# MFU_1_00.net
KiCad netlist of a schematic drawn in Altium Designer
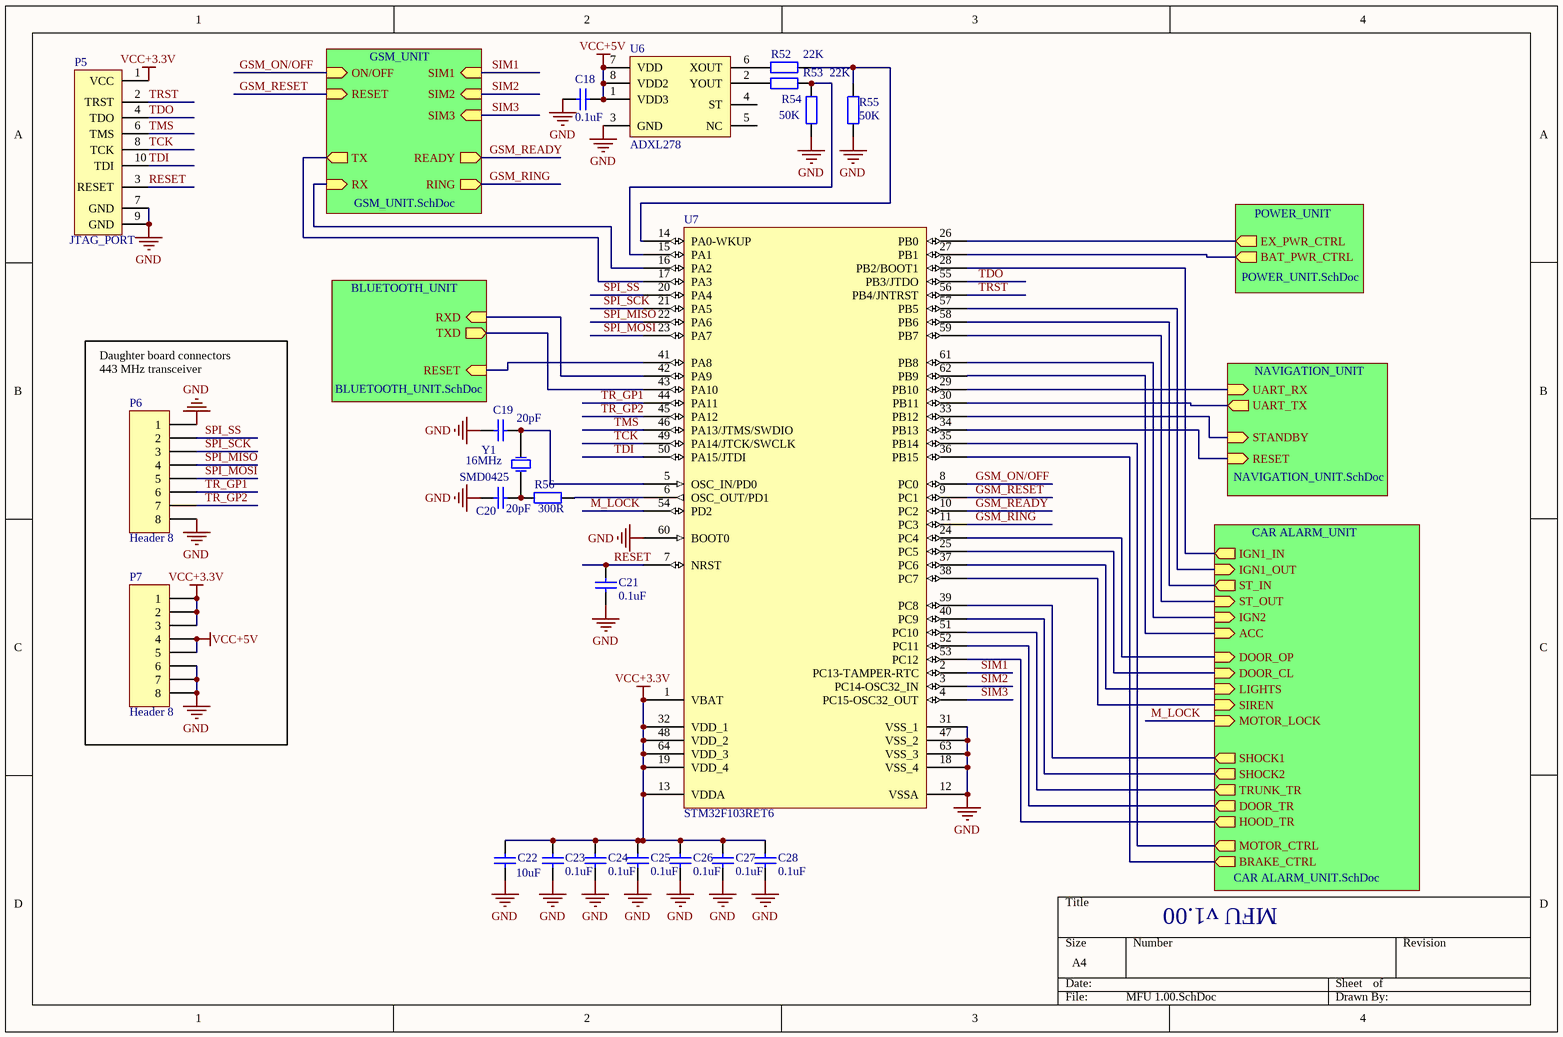
[diagram p0: MFU 1.00.SchDoc]

(export (version "E")
  (design (tool "Eeschema 10.0.6"))
  (components
    (comp (ref "C18")
      (value "0.1uF")
      (footprint "C0603")
      (description "Capasitor_SMD_0808/")
      (fields (field (name "Comment") "0805"))
      (libsource (lib "NEW") (part "Capasitor_SMD_0805"))
    )
    (comp (ref "C19")
      (value "20pF")
      (footprint "C0603")
      (description "Capasitor_SMD_0808/")
      (fields (field (name "Comment") "0805"))
      (libsource (lib "NEW") (part "Capasitor_SMD_0805"))
    )
    (comp (ref "C20")
      (value "20pF")
      (footprint "C0603")
      (description "Capasitor_SMD_0808/")
      (fields (field (name "Comment") "0805"))
      (libsource (lib "NEW") (part "Capasitor_SMD_0805"))
    )
    (comp (ref "C21")
      (value "0.1uF")
      (footprint "C0603")
      (description "Capasitor_SMD_0808/")
      (fields (field (name "Comment") "0805"))
      (libsource (lib "NEW") (part "Capasitor_SMD_0805"))
    )
    (comp (ref "C22")
      (value "10uF")
      (footprint "C1210")
      (description "Capacitor (Semiconductor SIM Model)")
      (fields (field (name "Comment") "Cap Semi") (field (name "PUBLISHER") "Altium Limited"))
      (libsource (lib "Miscellaneous Devices") (part "Cap Semi"))
    )
    (comp (ref "C23")
      (value "0.1uF")
      (footprint "C0603")
      (description "Capasitor_SMD_0808/")
      (fields (field (name "Comment") "0805"))
      (libsource (lib "NEW") (part "Capasitor_SMD_0805"))
    )
    (comp (ref "C24")
      (value "0.1uF")
      (footprint "C0603")
      (description "Capasitor_SMD_0808/")
      (fields (field (name "Comment") "0805"))
      (libsource (lib "NEW") (part "Capasitor_SMD_0805"))
    )
    (comp (ref "C25")
      (value "0.1uF")
      (footprint "C0603")
      (description "Capasitor_SMD_0808/")
      (fields (field (name "Comment") "0805"))
      (libsource (lib "NEW") (part "Capasitor_SMD_0805"))
    )
    (comp (ref "C26")
      (value "0.1uF")
      (footprint "C0603")
      (description "Capasitor_SMD_0808/")
      (fields (field (name "Comment") "0805"))
      (libsource (lib "NEW") (part "Capasitor_SMD_0805"))
    )
    (comp (ref "C27")
      (value "0.1uF")
      (footprint "C0603")
      (description "Capasitor_SMD_0808/")
      (fields (field (name "Comment") "0805"))
      (libsource (lib "NEW") (part "Capasitor_SMD_0805"))
    )
    (comp (ref "C28")
      (value "0.1uF")
      (footprint "C0603")
      (description "Capasitor_SMD_0808/")
      (fields (field (name "Comment") "0805"))
      (libsource (lib "NEW") (part "Capasitor_SMD_0805"))
    )
    (comp (ref "P5")
      (value "JTAG_PORT")
      (footprint "JTAG_connector")
      (libsource (lib "NEW") (part "JTAG_port"))
    )
    (comp (ref "P6")
      (value "Header 8")
      (footprint "HDR1X8")
      (description "Header, 8-Pin")
      (fields (field (name "PUBLISHER") "Altium Limited"))
      (libsource (lib "Miscellaneous Connectors") (part "Header 8"))
    )
    (comp (ref "P7")
      (value "Header 8")
      (footprint "HDR1X8")
      (description "Header, 8-Pin")
      (fields (field (name "PUBLISHER") "Altium Limited"))
      (libsource (lib "Miscellaneous Connectors") (part "Header 8"))
    )
    (comp (ref "R52")
      (value "22K")
      (footprint "C0603")
      (description "Resistor")
      (fields (field (name "Comment") "RES"))
      (libsource (lib "NEW") (part "RES"))
    )
    (comp (ref "R53")
      (value "22K")
      (footprint "C0603")
      (description "Resistor")
      (fields (field (name "Comment") "RES"))
      (libsource (lib "NEW") (part "RES"))
    )
    (comp (ref "R54")
      (value "50K")
      (footprint "C0603")
      (description "Resistor")
      (fields (field (name "Comment") "RES"))
      (libsource (lib "") (part "RES_2"))
    )
    (comp (ref "R55")
      (value "50K")
      (footprint "C0603")
      (description "Resistor")
      (fields (field (name "Comment") "RES"))
      (libsource (lib "") (part "RES_2"))
    )
    (comp (ref "R56")
      (value "300R")
      (footprint "C0603")
      (description "Resistor")
      (fields (field (name "Comment") "RES"))
      (libsource (lib "") (part "RES_1"))
    )
    (comp (ref "U6") (value "ADXL278") (footprint "ADXL278") (libsource (lib "NEW") (part "ADXL278")))
    (comp (ref "U7")
      (value "STM32F103RET6")
      (footprint "LQFP64_M")
      (description "STM32 ARM-based 32-bit MCU with 512 Kbytes Flash, 64-pin LQFP, Industrial Temperature")
      (fields (field (name "PUBLISHER") "Altium Limited"))
      (libsource (lib "ST Microcontroller 32-Bit STM32") (part "STM32F103RBT6"))
    )
    (comp (ref "Y1")
      (value "SMD0425")
      (footprint "QUARTZ_SMD0425")
      (fields (field (name "ALTIUM_VALUE") "16MHz"))
      (libsource (lib "NEW") (part "Quartz_SMD"))
    )
  )
  (nets
    (net (code "1") (name "/ACC") (class "Default")
      (node (ref "U7") (pin "62") (pinfunction "PB9_62") (pintype "bidirectional"))
    )
    (net (code "2") (name "/BAT_PWR_CTRL") (class "Default")
      (node (ref "U7") (pin "27") (pinfunction "PB1_27") (pintype "bidirectional"))
    )
    (net (code "3") (name "/BRAKE_CTRL") (class "Default")
      (node (ref "U7") (pin "36") (pinfunction "PB15_36") (pintype "bidirectional"))
    )
    (net (code "4") (name "/DOOR_CL") (class "Default")
      (node (ref "U7") (pin "25") (pinfunction "PC5_25") (pintype "bidirectional"))
    )
    (net (code "5") (name "/DOOR_OP") (class "Default")
      (node (ref "U7") (pin "24") (pinfunction "PC4_24") (pintype "bidirectional"))
    )
    (net (code "6") (name "/DOOR_TR") (class "Default")
      (node (ref "U7") (pin "52") (pinfunction "PC11_52") (pintype "bidirectional"))
    )
    (net (code "7") (name "/EX_PWR_CTRL") (class "Default")
      (node (ref "U7") (pin "26") (pinfunction "PB0_26") (pintype "bidirectional"))
    )
    (net (code "8") (name "/GSM_ON{slash}OFF") (class "Default")
      (node (ref "U7") (pin "8") (pinfunction "PC0_8") (pintype "bidirectional"))
    )
    (net (code "9") (name "/GSM_READY") (class "Default")
      (node (ref "U7") (pin "10") (pinfunction "PC2_10") (pintype "bidirectional"))
    )
    (net (code "10") (name "/GSM_RESET") (class "Default")
      (node (ref "U7") (pin "9") (pinfunction "PC1_9") (pintype "bidirectional"))
    )
    (net (code "11") (name "/GSM_RING") (class "Default")
      (node (ref "U7") (pin "11") (pinfunction "PC3_11") (pintype "bidirectional"))
    )
    (net (code "12") (name "/HOOD_TR") (class "Default")
      (node (ref "U7") (pin "53") (pinfunction "PC12_53") (pintype "bidirectional"))
    )
    (net (code "13") (name "/IGN1_IN") (class "Default")
      (node (ref "U7") (pin "28") (pinfunction "PB2/BOOT1_28") (pintype "bidirectional"))
    )
    (net (code "14") (name "/IGN1_OUT") (class "Default")
      (node (ref "U7") (pin "57") (pinfunction "PB5_57") (pintype "bidirectional"))
    )
    (net (code "15") (name "/IGN2") (class "Default")
      (node (ref "U7") (pin "61") (pinfunction "PB8_61") (pintype "bidirectional"))
    )
    (net (code "16") (name "/LIGHTS") (class "Default")
      (node (ref "U7") (pin "37") (pinfunction "PC6_37") (pintype "bidirectional"))
    )
    (net (code "17") (name "/MOTOR_CTRL") (class "Default")
      (node (ref "U7") (pin "35") (pinfunction "PB14_35") (pintype "bidirectional"))
    )
    (net (code "18") (name "/M_LOCK") (class "Default")
      (node (ref "U7") (pin "54") (pinfunction "PD2_54") (pintype "bidirectional"))
    )
    (net (code "19") (name "/RESET") (class "Default")
      (node (ref "C21") (pin "2") (pinfunction "2_2") (pintype "passive"))
      (node (ref "P5") (pin "3") (pinfunction "RESET_3") (pintype "passive"))
      (node (ref "U7") (pin "7") (pinfunction "NRST_7") (pintype "bidirectional"))
    )
    (net (code "20") (name "/RESET_1") (class "Default")
      (node (ref "U7") (pin "34") (pinfunction "PB13_34") (pintype "bidirectional"))
    )
    (net (code "21") (name "/RESET_2") (class "Default")
      (node (ref "U7") (pin "41") (pinfunction "PA8_41") (pintype "bidirectional"))
    )
    (net (code "22") (name "/RX") (class "Default")
      (node (ref "U7") (pin "16") (pinfunction "PA2_16") (pintype "bidirectional"))
    )
    (net (code "23") (name "/RXD") (class "Default")
      (node (ref "U7") (pin "42") (pinfunction "PA9_42") (pintype "bidirectional"))
    )
    (net (code "24") (name "/SHOCK1") (class "Default")
      (node (ref "U7") (pin "39") (pinfunction "PC8_39") (pintype "bidirectional"))
    )
    (net (code "25") (name "/SHOCK2") (class "Default")
      (node (ref "U7") (pin "40") (pinfunction "PC9_40") (pintype "bidirectional"))
    )
    (net (code "26") (name "/SIM1") (class "Default")
      (node (ref "U7") (pin "2") (pinfunction "PC13-TAMPER-RTC_2") (pintype "bidirectional"))
    )
    (net (code "27") (name "/SIM2") (class "Default")
      (node (ref "U7") (pin "3") (pinfunction "PC14-OSC32_IN_3") (pintype "bidirectional"))
    )
    (net (code "28") (name "/SIM3") (class "Default")
      (node (ref "U7") (pin "4") (pinfunction "PC15-OSC32_OUT_4") (pintype "bidirectional"))
    )
    (net (code "29") (name "/SIREN") (class "Default")
      (node (ref "U7") (pin "38") (pinfunction "PC7_38") (pintype "bidirectional"))
    )
    (net (code "30") (name "/SPI_MISO") (class "Default")
      (node (ref "P6") (pin "4") (pinfunction "4_4") (pintype "passive"))
      (node (ref "U7") (pin "22") (pinfunction "PA6_22") (pintype "bidirectional"))
    )
    (net (code "31") (name "/SPI_MOSI") (class "Default")
      (node (ref "P6") (pin "5") (pinfunction "5_5") (pintype "passive"))
      (node (ref "U7") (pin "23") (pinfunction "PA7_23") (pintype "bidirectional"))
    )
    (net (code "32") (name "/SPI_SCK") (class "Default")
      (node (ref "P6") (pin "3") (pinfunction "3_3") (pintype "passive"))
      (node (ref "U7") (pin "21") (pinfunction "PA5_21") (pintype "bidirectional"))
    )
    (net (code "33") (name "/SPI_SS") (class "Default")
      (node (ref "P6") (pin "2") (pinfunction "2_2") (pintype "passive"))
      (node (ref "U7") (pin "20") (pinfunction "PA4_20") (pintype "bidirectional"))
    )
    (net (code "34") (name "/STANDBY") (class "Default")
      (node (ref "U7") (pin "33") (pinfunction "PB12_33") (pintype "bidirectional"))
    )
    (net (code "35") (name "/ST_IN") (class "Default")
      (node (ref "U7") (pin "58") (pinfunction "PB6_58") (pintype "bidirectional"))
    )
    (net (code "36") (name "/ST_OUT") (class "Default")
      (node (ref "U7") (pin "59") (pinfunction "PB7_59") (pintype "bidirectional"))
    )
    (net (code "37") (name "/TCK") (class "Default")
      (node (ref "P5") (pin "8") (pinfunction "TCK_8") (pintype "passive"))
      (node (ref "U7") (pin "49") (pinfunction "PA14/JTCK/SWCLK_49") (pintype "bidirectional"))
    )
    (net (code "38") (name "/TDI") (class "Default")
      (node (ref "P5") (pin "10") (pinfunction "TDI_10") (pintype "passive"))
      (node (ref "U7") (pin "50") (pinfunction "PA15/JTDI_50") (pintype "bidirectional"))
    )
    (net (code "39") (name "/TDO") (class "Default")
      (node (ref "P5") (pin "4") (pinfunction "TDO_4") (pintype "passive"))
      (node (ref "U7") (pin "55") (pinfunction "PB3/JTDO_55") (pintype "bidirectional"))
    )
    (net (code "40") (name "/TMS") (class "Default")
      (node (ref "P5") (pin "6") (pinfunction "TMS_6") (pintype "passive"))
      (node (ref "U7") (pin "46") (pinfunction "PA13/JTMS/SWDIO_46") (pintype "bidirectional"))
    )
    (net (code "41") (name "/TRST") (class "Default")
      (node (ref "P5") (pin "2") (pinfunction "TRST_2") (pintype "passive"))
      (node (ref "U7") (pin "56") (pinfunction "PB4/JNTRST_56") (pintype "bidirectional"))
    )
    (net (code "42") (name "/TRUNK_TR") (class "Default")
      (node (ref "U7") (pin "51") (pinfunction "PC10_51") (pintype "bidirectional"))
    )
    (net (code "43") (name "/TR_GP1") (class "Default")
      (node (ref "P6") (pin "6") (pinfunction "6_6") (pintype "passive"))
      (node (ref "U7") (pin "44") (pinfunction "PA11_44") (pintype "bidirectional"))
    )
    (net (code "44") (name "/TR_GP2") (class "Default")
      (node (ref "P6") (pin "7") (pinfunction "7_7") (pintype "passive"))
      (node (ref "U7") (pin "45") (pinfunction "PA12_45") (pintype "bidirectional"))
    )
    (net (code "45") (name "/TX") (class "Default")
      (node (ref "U7") (pin "17") (pinfunction "PA3_17") (pintype "bidirectional"))
    )
    (net (code "46") (name "/TXD") (class "Default")
      (node (ref "U7") (pin "43") (pinfunction "PA10_43") (pintype "bidirectional"))
    )
    (net (code "47") (name "/UART_RX") (class "Default")
      (node (ref "U7") (pin "29") (pinfunction "PB10_29") (pintype "bidirectional"))
    )
    (net (code "48") (name "/UART_TX") (class "Default")
      (node (ref "U7") (pin "30") (pinfunction "PB11_30") (pintype "bidirectional"))
    )
    (net (code "49") (name "GND") (class "Default")
      (node (ref "C18") (pin "1") (pinfunction "1_1") (pintype "passive"))
      (node (ref "C19") (pin "2") (pinfunction "2_2") (pintype "passive"))
      (node (ref "C20") (pin "2") (pinfunction "2_2") (pintype "passive"))
      (node (ref "C21") (pin "1") (pinfunction "1_1") (pintype "passive"))
      (node (ref "C22") (pin "1") (pinfunction "1_1") (pintype "passive"))
      (node (ref "C23") (pin "1") (pinfunction "1_1") (pintype "passive"))
      (node (ref "C24") (pin "1") (pinfunction "1_1") (pintype "passive"))
      (node (ref "C25") (pin "1") (pinfunction "1_1") (pintype "passive"))
      (node (ref "C26") (pin "1") (pinfunction "1_1") (pintype "passive"))
      (node (ref "C27") (pin "1") (pinfunction "1_1") (pintype "passive"))
      (node (ref "C28") (pin "1") (pinfunction "1_1") (pintype "passive"))
      (node (ref "P5") (pin "7") (pinfunction "GND_7") (pintype "passive"))
      (node (ref "P5") (pin "9") (pinfunction "GND_9") (pintype "passive"))
      (node (ref "P6") (pin "1") (pinfunction "1_1") (pintype "passive"))
      (node (ref "P6") (pin "8") (pinfunction "8_8") (pintype "passive"))
      (node (ref "P7") (pin "6") (pinfunction "6_6") (pintype "passive"))
      (node (ref "P7") (pin "7") (pinfunction "7_7") (pintype "passive"))
      (node (ref "P7") (pin "8") (pinfunction "8_8") (pintype "passive"))
      (node (ref "R54") (pin "2") (pinfunction "2_2") (pintype "passive"))
      (node (ref "R55") (pin "2") (pinfunction "2_2") (pintype "passive"))
      (node (ref "U6") (pin "3") (pinfunction "GND_3") (pintype "passive"))
      (node (ref "U7") (pin "12") (pinfunction "VSSA_12") (pintype "power_in"))
      (node (ref "U7") (pin "18") (pinfunction "VSS_4_18") (pintype "power_in"))
      (node (ref "U7") (pin "31") (pinfunction "VSS_1_31") (pintype "power_in"))
      (node (ref "U7") (pin "47") (pinfunction "VSS_2_47") (pintype "power_in"))
      (node (ref "U7") (pin "60") (pinfunction "BOOT0_60") (pintype "input"))
      (node (ref "U7") (pin "63") (pinfunction "VSS_3_63") (pintype "power_in"))
    )
    (net (code "50") (name "Net-(U6-XOUT)") (class "Default")
      (node (ref "R52") (pin "2") (pinfunction "2_2") (pintype "passive"))
      (node (ref "U6") (pin "6") (pinfunction "XOUT_6") (pintype "passive"))
    )
    (net (code "51") (name "Net-(U6-YOUT)") (class "Default")
      (node (ref "R53") (pin "2") (pinfunction "2_2") (pintype "passive"))
      (node (ref "U6") (pin "2") (pinfunction "YOUT_2") (pintype "passive"))
    )
    (net (code "52") (name "Net-(U7-OSC_IN{slash}PD0)") (class "Default")
      (node (ref "C19") (pin "1") (pinfunction "1_1") (pintype "passive"))
      (node (ref "U7") (pin "5") (pinfunction "OSC_IN/PD0_5") (pintype "input"))
      (node (ref "Y1") (pin "3") (pinfunction "OSC2_3") (pintype "passive"))
    )
    (net (code "53") (name "Net-(U7-OSC_OUT{slash}PD1)") (class "Default")
      (node (ref "R56") (pin "2") (pinfunction "2_2") (pintype "passive"))
      (node (ref "U7") (pin "6") (pinfunction "OSC_OUT/PD1_6") (pintype "output"))
    )
    (net (code "54") (name "Net-(U7-PA0-WKUP)") (class "Default")
      (node (ref "R52") (pin "1") (pinfunction "1_1") (pintype "passive"))
      (node (ref "R55") (pin "1") (pinfunction "1_1") (pintype "passive"))
      (node (ref "U7") (pin "14") (pinfunction "PA0-WKUP_14") (pintype "bidirectional"))
    )
    (net (code "55") (name "Net-(U7-PA1)") (class "Default")
      (node (ref "R53") (pin "1") (pinfunction "1_1") (pintype "passive"))
      (node (ref "R54") (pin "1") (pinfunction "1_1") (pintype "passive"))
      (node (ref "U7") (pin "15") (pinfunction "PA1_15") (pintype "bidirectional"))
    )
    (net (code "56") (name "Net-(Y1-OSC1)") (class "Default")
      (node (ref "C20") (pin "1") (pinfunction "1_1") (pintype "passive"))
      (node (ref "R56") (pin "1") (pinfunction "1_1") (pintype "passive"))
      (node (ref "Y1") (pin "1") (pinfunction "OSC1_1") (pintype "passive"))
    )
    (net (code "57") (name "VCC+3.3V") (class "Default")
      (node (ref "C22") (pin "2") (pinfunction "2_2") (pintype "passive"))
      (node (ref "C23") (pin "2") (pinfunction "2_2") (pintype "passive"))
      (node (ref "C24") (pin "2") (pinfunction "2_2") (pintype "passive"))
      (node (ref "C25") (pin "2") (pinfunction "2_2") (pintype "passive"))
      (node (ref "C26") (pin "2") (pinfunction "2_2") (pintype "passive"))
      (node (ref "C27") (pin "2") (pinfunction "2_2") (pintype "passive"))
      (node (ref "C28") (pin "2") (pinfunction "2_2") (pintype "passive"))
      (node (ref "P5") (pin "1") (pinfunction "VCC_1") (pintype "passive"))
      (node (ref "P7") (pin "1") (pinfunction "1_1") (pintype "passive"))
      (node (ref "P7") (pin "2") (pinfunction "2_2") (pintype "passive"))
      (node (ref "P7") (pin "3") (pinfunction "3_3") (pintype "passive"))
      (node (ref "U7") (pin "1") (pinfunction "VBAT_1") (pintype "power_in"))
      (node (ref "U7") (pin "13") (pinfunction "VDDA_13") (pintype "power_in"))
      (node (ref "U7") (pin "19") (pinfunction "VDD_4_19") (pintype "power_in"))
      (node (ref "U7") (pin "32") (pinfunction "VDD_1_32") (pintype "power_in"))
      (node (ref "U7") (pin "48") (pinfunction "VDD_2_48") (pintype "power_in"))
      (node (ref "U7") (pin "64") (pinfunction "VDD_3_64") (pintype "power_in"))
    )
    (net (code "58") (name "VCC+5V") (class "Default")
      (node (ref "C18") (pin "2") (pinfunction "2_2") (pintype "passive"))
      (node (ref "P7") (pin "4") (pinfunction "4_4") (pintype "passive"))
      (node (ref "P7") (pin "5") (pinfunction "5_5") (pintype "passive"))
      (node (ref "U6") (pin "1") (pinfunction "VDD3_1") (pintype "passive"))
      (node (ref "U6") (pin "7") (pinfunction "VDD_7") (pintype "passive"))
      (node (ref "U6") (pin "8") (pinfunction "VDD2_8") (pintype "passive"))
    )
    (net (code "59") (name "unconnected-(U6-NC-Pad5)") (class "Default")
      (node (ref "U6") (pin "5") (pinfunction "NC_5") (pintype "passive"))
    )
    (net (code "60") (name "unconnected-(U6-ST-Pad4)") (class "Default")
      (node (ref "U6") (pin "4") (pinfunction "ST_4") (pintype "passive"))
    )
  )
)
